# ADCIN_ACcoupled_ETC1-1-13.net
KiCad netlist of a schematic drawn in Altium Designer
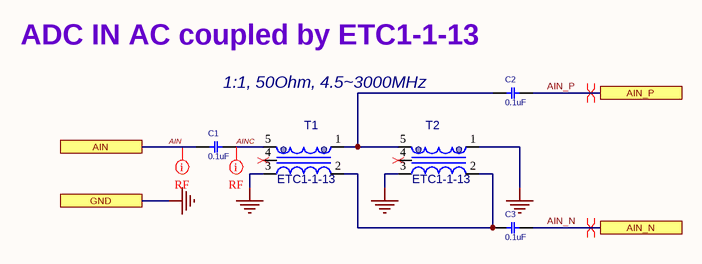
[diagram p0: ADCIN_ACcoupled_ETC1-1-13.SchDoc]

(export (version "E")
  (design (tool "Eeschema 10.0.6"))
  (components
    (comp (ref "C1")
      (value "0.1uF")
      (footprint "C0402")
      (description "CAP, MLCC, 100nF, 50V, X7R, 10%, 0402C")
      (fields (field (name "MANF_P#") "GCM155R71H104KE02D") (field (name "MANF") "Murata"))
      (libsource (lib "mlcc_smd_passive") (part "CAP_SMD_MLCC_100n50TDK"))
    )
    (comp (ref "C2")
      (value "0.1uF")
      (footprint "C0402")
      (description "CAP, MLCC, 100nF, 50V, X7R, 10%, 0402C")
      (fields (field (name "MANF_P#") "GCM155R71H104KE02D") (field (name "MANF") "Murata"))
      (libsource (lib "mlcc_smd_passive") (part "CAP_SMD_MLCC_100n50TDK"))
    )
    (comp (ref "C3")
      (value "0.1uF")
      (footprint "C0402")
      (description "CAP, MLCC, 100nF, 50V, X7R, 10%, 0402C")
      (fields (field (name "MANF_P#") "GCM155R71H104KE02D") (field (name "MANF") "Murata"))
      (libsource (lib "mlcc_smd_passive") (part "CAP_SMD_MLCC_100n50TDK"))
    )
    (comp (ref "T1")
      (value "ETC1-1-13")
      (footprint "TRNS_ETC1_1_13")
      (description "RF Transformer, 1:1, 50Ohm, 4.5~3000MHz")
      (fields (field (name "MANF") "MACOM"))
      (libsource (lib "transformer_rf") (part "ETC1-1-13"))
    )
    (comp (ref "T2")
      (value "ETC1-1-13")
      (footprint "TRNS_ETC1_1_13")
      (description "RF Transformer, 1:1, 50Ohm, 4.5~3000MHz")
      (fields (field (name "MANF") "MACOM"))
      (libsource (lib "transformer_rf") (part "ETC1-1-13"))
    )
  )
  (nets
    (net (code "1") (name "/AIN") (class "Default")
      (node (ref "C1") (pin "1") (pinfunction "1_1") (pintype "passive"))
    )
    (net (code "2") (name "/AINC") (class "Default")
      (node (ref "C1") (pin "2") (pinfunction "2_2") (pintype "passive"))
      (node (ref "T1") (pin "5") (pinfunction "SEC._5") (pintype "passive"))
    )
    (net (code "3") (name "/AIN_N") (class "Default")
      (node (ref "C3") (pin "2") (pinfunction "2_2") (pintype "passive"))
    )
    (net (code "4") (name "/AIN_P") (class "Default")
      (node (ref "C2") (pin "2") (pinfunction "2_2") (pintype "passive"))
    )
    (net (code "5") (name "GND") (class "Default")
      (node (ref "T1") (pin "3") (pinfunction "SEC_3") (pintype "passive"))
      (node (ref "T2") (pin "1") (pinfunction "PRI._1") (pintype "passive"))
      (node (ref "T2") (pin "3") (pinfunction "SEC_3") (pintype "passive"))
    )
    (net (code "6") (name "Net-(T1-PRI)") (class "Default")
      (node (ref "C3") (pin "1") (pinfunction "1_1") (pintype "passive"))
      (node (ref "T1") (pin "2") (pinfunction "PRI_2") (pintype "passive"))
      (node (ref "T2") (pin "2") (pinfunction "PRI_2") (pintype "passive"))
    )
    (net (code "7") (name "Net-(T1-PRI.)") (class "Default")
      (node (ref "C2") (pin "1") (pinfunction "1_1") (pintype "passive"))
      (node (ref "T1") (pin "1") (pinfunction "PRI._1") (pintype "passive"))
      (node (ref "T2") (pin "5") (pinfunction "SEC._5") (pintype "passive"))
    )
    (net (code "8") (name "unconnected-(T1-Pad4)") (class "Default")
      (node (ref "T1") (pin "4") (pinfunction "4_4") (pintype "passive"))
    )
    (net (code "9") (name "unconnected-(T2-Pad4)") (class "Default")
      (node (ref "T2") (pin "4") (pinfunction "4_4") (pintype "passive"))
    )
  )
)
